# IDC50ToSensor.net
KiCad netlist of a schematic drawn in Altium Designer
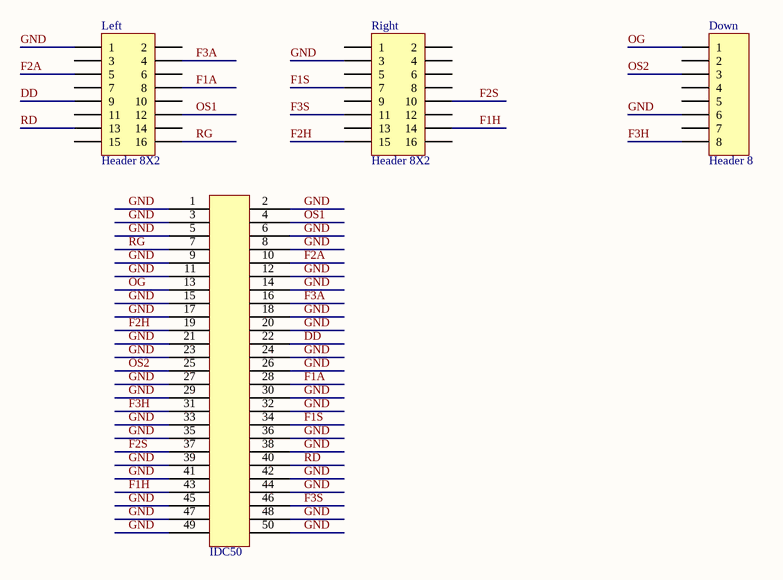
[diagram p0: IDC50ToSensor.SchDoc]

(export (version "E")
  (design (tool "Eeschema 10.0.6"))
  (components
    (comp (ref "*") (value "IDC50") (footprint "IDC50") (libsource (lib "eic_lib") (part "IDC50")))
    (comp (ref "Down")
      (value "Header 8")
      (footprint "HDR1X8")
      (description "Header, 8-Pin")
      (fields (field (name "PUBLISHER") "Altium Limited"))
      (libsource (lib "Miscellaneous Connectors") (part "Header 8"))
    )
    (comp (ref "Left")
      (value "Header 8X2")
      (footprint "HDR2X8")
      (description "Header, 8-Pin, Dual row")
      (fields (field (name "PUBLISHER") "Altium Limited"))
      (libsource (lib "Miscellaneous Connectors") (part "Header 8X2"))
    )
    (comp (ref "Right")
      (value "Header 8X2")
      (footprint "HDR2X8")
      (description "Header, 8-Pin, Dual row")
      (fields (field (name "PUBLISHER") "Altium Limited"))
      (libsource (lib "Miscellaneous Connectors") (part "Header 8X2"))
    )
  )
  (nets
    (net (code "1") (name "/DD") (class "Default")
      (node (ref "*") (pin "22") (pintype "passive"))
      (node (ref "Left") (pin "9") (pinfunction "9_9") (pintype "passive"))
    )
    (net (code "2") (name "/F1A") (class "Default")
      (node (ref "*") (pin "28") (pintype "passive"))
      (node (ref "Left") (pin "8") (pinfunction "8_8") (pintype "passive"))
    )
    (net (code "3") (name "/F1H") (class "Default")
      (node (ref "*") (pin "43") (pintype "passive"))
      (node (ref "Right") (pin "14") (pinfunction "14_14") (pintype "passive"))
    )
    (net (code "4") (name "/F1S") (class "Default")
      (node (ref "*") (pin "34") (pintype "passive"))
      (node (ref "Right") (pin "7") (pinfunction "7_7") (pintype "passive"))
    )
    (net (code "5") (name "/F2A") (class "Default")
      (node (ref "*") (pin "10") (pintype "passive"))
      (node (ref "Left") (pin "5") (pinfunction "5_5") (pintype "passive"))
    )
    (net (code "6") (name "/F2H") (class "Default")
      (node (ref "*") (pin "19") (pintype "passive"))
      (node (ref "Right") (pin "15") (pinfunction "15_15") (pintype "passive"))
    )
    (net (code "7") (name "/F2S") (class "Default")
      (node (ref "*") (pin "37") (pintype "passive"))
      (node (ref "Right") (pin "10") (pinfunction "10_10") (pintype "passive"))
    )
    (net (code "8") (name "/F3A") (class "Default")
      (node (ref "*") (pin "16") (pintype "passive"))
      (node (ref "Left") (pin "4") (pinfunction "4_4") (pintype "passive"))
    )
    (net (code "9") (name "/F3H") (class "Default")
      (node (ref "*") (pin "31") (pintype "passive"))
      (node (ref "Down") (pin "8") (pinfunction "8_8") (pintype "passive"))
    )
    (net (code "10") (name "/F3S") (class "Default")
      (node (ref "*") (pin "46") (pintype "passive"))
      (node (ref "Right") (pin "11") (pinfunction "11_11") (pintype "passive"))
    )
    (net (code "11") (name "/GND") (class "Default")
      (node (ref "*") (pin "1") (pintype "passive"))
      (node (ref "*") (pin "11") (pintype "passive"))
      (node (ref "*") (pin "12") (pintype "passive"))
      (node (ref "*") (pin "14") (pintype "passive"))
      (node (ref "*") (pin "15") (pintype "passive"))
      (node (ref "*") (pin "17") (pintype "passive"))
      (node (ref "*") (pin "18") (pintype "passive"))
      (node (ref "*") (pin "2") (pintype "passive"))
      (node (ref "*") (pin "20") (pintype "passive"))
      (node (ref "*") (pin "21") (pintype "passive"))
      (node (ref "*") (pin "23") (pintype "passive"))
      (node (ref "*") (pin "24") (pintype "passive"))
      (node (ref "*") (pin "26") (pintype "passive"))
      (node (ref "*") (pin "27") (pintype "passive"))
      (node (ref "*") (pin "29") (pintype "passive"))
      (node (ref "*") (pin "3") (pintype "passive"))
      (node (ref "*") (pin "30") (pintype "passive"))
      (node (ref "*") (pin "32") (pintype "passive"))
      (node (ref "*") (pin "33") (pintype "passive"))
      (node (ref "*") (pin "35") (pintype "passive"))
      (node (ref "*") (pin "36") (pintype "passive"))
      (node (ref "*") (pin "38") (pintype "passive"))
      (node (ref "*") (pin "39") (pintype "passive"))
      (node (ref "*") (pin "41") (pintype "passive"))
      (node (ref "*") (pin "42") (pintype "passive"))
      (node (ref "*") (pin "44") (pintype "passive"))
      (node (ref "*") (pin "45") (pintype "passive"))
      (node (ref "*") (pin "47") (pintype "passive"))
      (node (ref "*") (pin "48") (pintype "passive"))
      (node (ref "*") (pin "49") (pintype "passive"))
      (node (ref "*") (pin "5") (pintype "passive"))
      (node (ref "*") (pin "50") (pintype "passive"))
      (node (ref "*") (pin "6") (pintype "passive"))
      (node (ref "*") (pin "8") (pintype "passive"))
      (node (ref "*") (pin "9") (pintype "passive"))
      (node (ref "Down") (pin "6") (pinfunction "6_6") (pintype "passive"))
      (node (ref "Left") (pin "1") (pinfunction "1_1") (pintype "passive"))
      (node (ref "Right") (pin "3") (pinfunction "3_3") (pintype "passive"))
    )
    (net (code "12") (name "/OG") (class "Default")
      (node (ref "*") (pin "13") (pintype "passive"))
      (node (ref "Down") (pin "1") (pinfunction "1_1") (pintype "passive"))
    )
    (net (code "13") (name "/OS1") (class "Default")
      (node (ref "*") (pin "4") (pintype "passive"))
      (node (ref "Left") (pin "12") (pinfunction "12_12") (pintype "passive"))
    )
    (net (code "14") (name "/OS2") (class "Default")
      (node (ref "*") (pin "25") (pintype "passive"))
      (node (ref "Down") (pin "3") (pinfunction "3_3") (pintype "passive"))
    )
    (net (code "15") (name "/RD") (class "Default")
      (node (ref "*") (pin "40") (pintype "passive"))
      (node (ref "Left") (pin "13") (pinfunction "13_13") (pintype "passive"))
    )
    (net (code "16") (name "/RG") (class "Default")
      (node (ref "*") (pin "7") (pintype "passive"))
      (node (ref "Left") (pin "16") (pinfunction "16_16") (pintype "passive"))
    )
    (net (code "17") (name "unconnected-(Down-Pad2)") (class "Default")
      (node (ref "Down") (pin "2") (pinfunction "2_2") (pintype "passive"))
    )
    (net (code "18") (name "unconnected-(Down-Pad4)") (class "Default")
      (node (ref "Down") (pin "4") (pinfunction "4_4") (pintype "passive"))
    )
    (net (code "19") (name "unconnected-(Down-Pad5)") (class "Default")
      (node (ref "Down") (pin "5") (pinfunction "5_5") (pintype "passive"))
    )
    (net (code "20") (name "unconnected-(Down-Pad7)") (class "Default")
      (node (ref "Down") (pin "7") (pinfunction "7_7") (pintype "passive"))
    )
    (net (code "21") (name "unconnected-(Left-Pad2)") (class "Default")
      (node (ref "Left") (pin "2") (pinfunction "2_2") (pintype "passive"))
    )
    (net (code "22") (name "unconnected-(Left-Pad3)") (class "Default")
      (node (ref "Left") (pin "3") (pinfunction "3_3") (pintype "passive"))
    )
    (net (code "23") (name "unconnected-(Left-Pad6)") (class "Default")
      (node (ref "Left") (pin "6") (pinfunction "6_6") (pintype "passive"))
    )
    (net (code "24") (name "unconnected-(Left-Pad7)") (class "Default")
      (node (ref "Left") (pin "7") (pinfunction "7_7") (pintype "passive"))
    )
    (net (code "25") (name "unconnected-(Left-Pad10)") (class "Default")
      (node (ref "Left") (pin "10") (pinfunction "10_10") (pintype "passive"))
    )
    (net (code "26") (name "unconnected-(Left-Pad11)") (class "Default")
      (node (ref "Left") (pin "11") (pinfunction "11_11") (pintype "passive"))
    )
    (net (code "27") (name "unconnected-(Left-Pad14)") (class "Default")
      (node (ref "Left") (pin "14") (pinfunction "14_14") (pintype "passive"))
    )
    (net (code "28") (name "unconnected-(Left-Pad15)") (class "Default")
      (node (ref "Left") (pin "15") (pinfunction "15_15") (pintype "passive"))
    )
    (net (code "29") (name "unconnected-(Right-Pad1)") (class "Default")
      (node (ref "Right") (pin "1") (pinfunction "1_1") (pintype "passive"))
    )
    (net (code "30") (name "unconnected-(Right-Pad2)") (class "Default")
      (node (ref "Right") (pin "2") (pinfunction "2_2") (pintype "passive"))
    )
    (net (code "31") (name "unconnected-(Right-Pad4)") (class "Default")
      (node (ref "Right") (pin "4") (pinfunction "4_4") (pintype "passive"))
    )
    (net (code "32") (name "unconnected-(Right-Pad5)") (class "Default")
      (node (ref "Right") (pin "5") (pinfunction "5_5") (pintype "passive"))
    )
    (net (code "33") (name "unconnected-(Right-Pad6)") (class "Default")
      (node (ref "Right") (pin "6") (pinfunction "6_6") (pintype "passive"))
    )
    (net (code "34") (name "unconnected-(Right-Pad8)") (class "Default")
      (node (ref "Right") (pin "8") (pinfunction "8_8") (pintype "passive"))
    )
    (net (code "35") (name "unconnected-(Right-Pad9)") (class "Default")
      (node (ref "Right") (pin "9") (pinfunction "9_9") (pintype "passive"))
    )
    (net (code "36") (name "unconnected-(Right-Pad12)") (class "Default")
      (node (ref "Right") (pin "12") (pinfunction "12_12") (pintype "passive"))
    )
    (net (code "37") (name "unconnected-(Right-Pad13)") (class "Default")
      (node (ref "Right") (pin "13") (pinfunction "13_13") (pintype "passive"))
    )
    (net (code "38") (name "unconnected-(Right-Pad16)") (class "Default")
      (node (ref "Right") (pin "16") (pinfunction "16_16") (pintype "passive"))
    )
  )
)
